# sensor.net
KiCad netlist of a schematic drawn in EAGLE
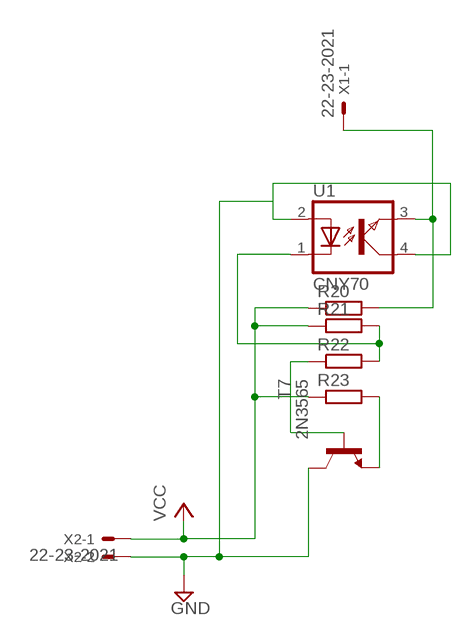
[diagram p0: schematic, sheet 1]

(export (version "E")
  (design (tool "Eeschema 10.0.6"))
  (components
    (comp (ref "R20")
      (value "R-EU_0204/7")
      (footprint "eagle-import:0204_7")
      (libsource (lib "eagle-import") (part "R-EU_0204/7"))
    )
    (comp (ref "R21")
      (value "R-EU_0204/7")
      (footprint "eagle-import:0204_7")
      (libsource (lib "eagle-import") (part "R-EU_0204/7"))
    )
    (comp (ref "R22")
      (value "R-EU_0204/7")
      (footprint "eagle-import:0204_7")
      (libsource (lib "eagle-import") (part "R-EU_0204/7"))
    )
    (comp (ref "R23")
      (value "R-EU_0204/7")
      (footprint "eagle-import:0204_7")
      (libsource (lib "eagle-import") (part "R-EU_0204/7"))
    )
    (comp (ref "T7")
      (value "2N3565")
      (footprint "eagle-import:TO92")
      (libsource (lib "eagle-import") (part "2N3565"))
    )
    (comp (ref "U1")
      (value "CNY70")
      (footprint "eagle-import:CNY70")
      (libsource (lib "eagle-import") (part "CNY70"))
    )
    (comp (ref "X1")
      (value "22-23-2021")
      (footprint "eagle-import:22-23-2021")
      (fields (field (name "MF") "MOLEX"))
      (libsource (lib "eagle-import") (part "22-23-2021"))
    )
    (comp (ref "X2")
      (value "22-23-2021")
      (footprint "eagle-import:22-23-2021")
      (fields (field (name "MF") "MOLEX"))
      (libsource (lib "eagle-import") (part "22-23-2021"))
    )
  )
  (nets
    (net (code "1") (name "GND") (class "Default")
      (node (ref "T7") (pin "1") (pinfunction "C_1") (pintype "passive"))
      (node (ref "U1") (pin "2") (pinfunction "2_2") (pintype "passive"))
      (node (ref "U1") (pin "4") (pinfunction "4_4") (pintype "passive"))
      (node (ref "X2") (pin "2") (pinfunction "S_2") (pintype "passive"))
    )
    (net (code "2") (name "Net-(R21-Pad2)") (class "Default")
      (node (ref "R21") (pin "2") (pinfunction "2_2") (pintype "passive"))
      (node (ref "R22") (pin "2") (pinfunction "2_2") (pintype "passive"))
      (node (ref "U1") (pin "1") (pinfunction "1_1") (pintype "passive"))
    )
    (net (code "3") (name "Net-(T7-B)") (class "Default")
      (node (ref "R22") (pin "1") (pinfunction "1_1") (pintype "passive"))
      (node (ref "T7") (pin "2") (pinfunction "B_2") (pintype "passive"))
    )
    (net (code "4") (name "Net-(T7-E)") (class "Default")
      (node (ref "R23") (pin "2") (pinfunction "2_2") (pintype "passive"))
      (node (ref "T7") (pin "3") (pinfunction "E_3") (pintype "passive"))
    )
    (net (code "5") (name "Net-(X1A-S)") (class "Default")
      (node (ref "R20") (pin "2") (pinfunction "2_2") (pintype "passive"))
      (node (ref "U1") (pin "3") (pinfunction "3_3") (pintype "passive"))
      (node (ref "X1") (pin "1") (pinfunction "S_1") (pintype "passive"))
    )
    (net (code "6") (name "VCC") (class "Default")
      (node (ref "R20") (pin "1") (pinfunction "1_1") (pintype "passive"))
      (node (ref "R21") (pin "1") (pinfunction "1_1") (pintype "passive"))
      (node (ref "R23") (pin "1") (pinfunction "1_1") (pintype "passive"))
      (node (ref "X2") (pin "1") (pinfunction "S_1") (pintype "passive"))
    )
  )
)
